# Capacitor_Thermal_Gradient_Test_Board.net
KiCad netlist of a schematic drawn in EAGLE
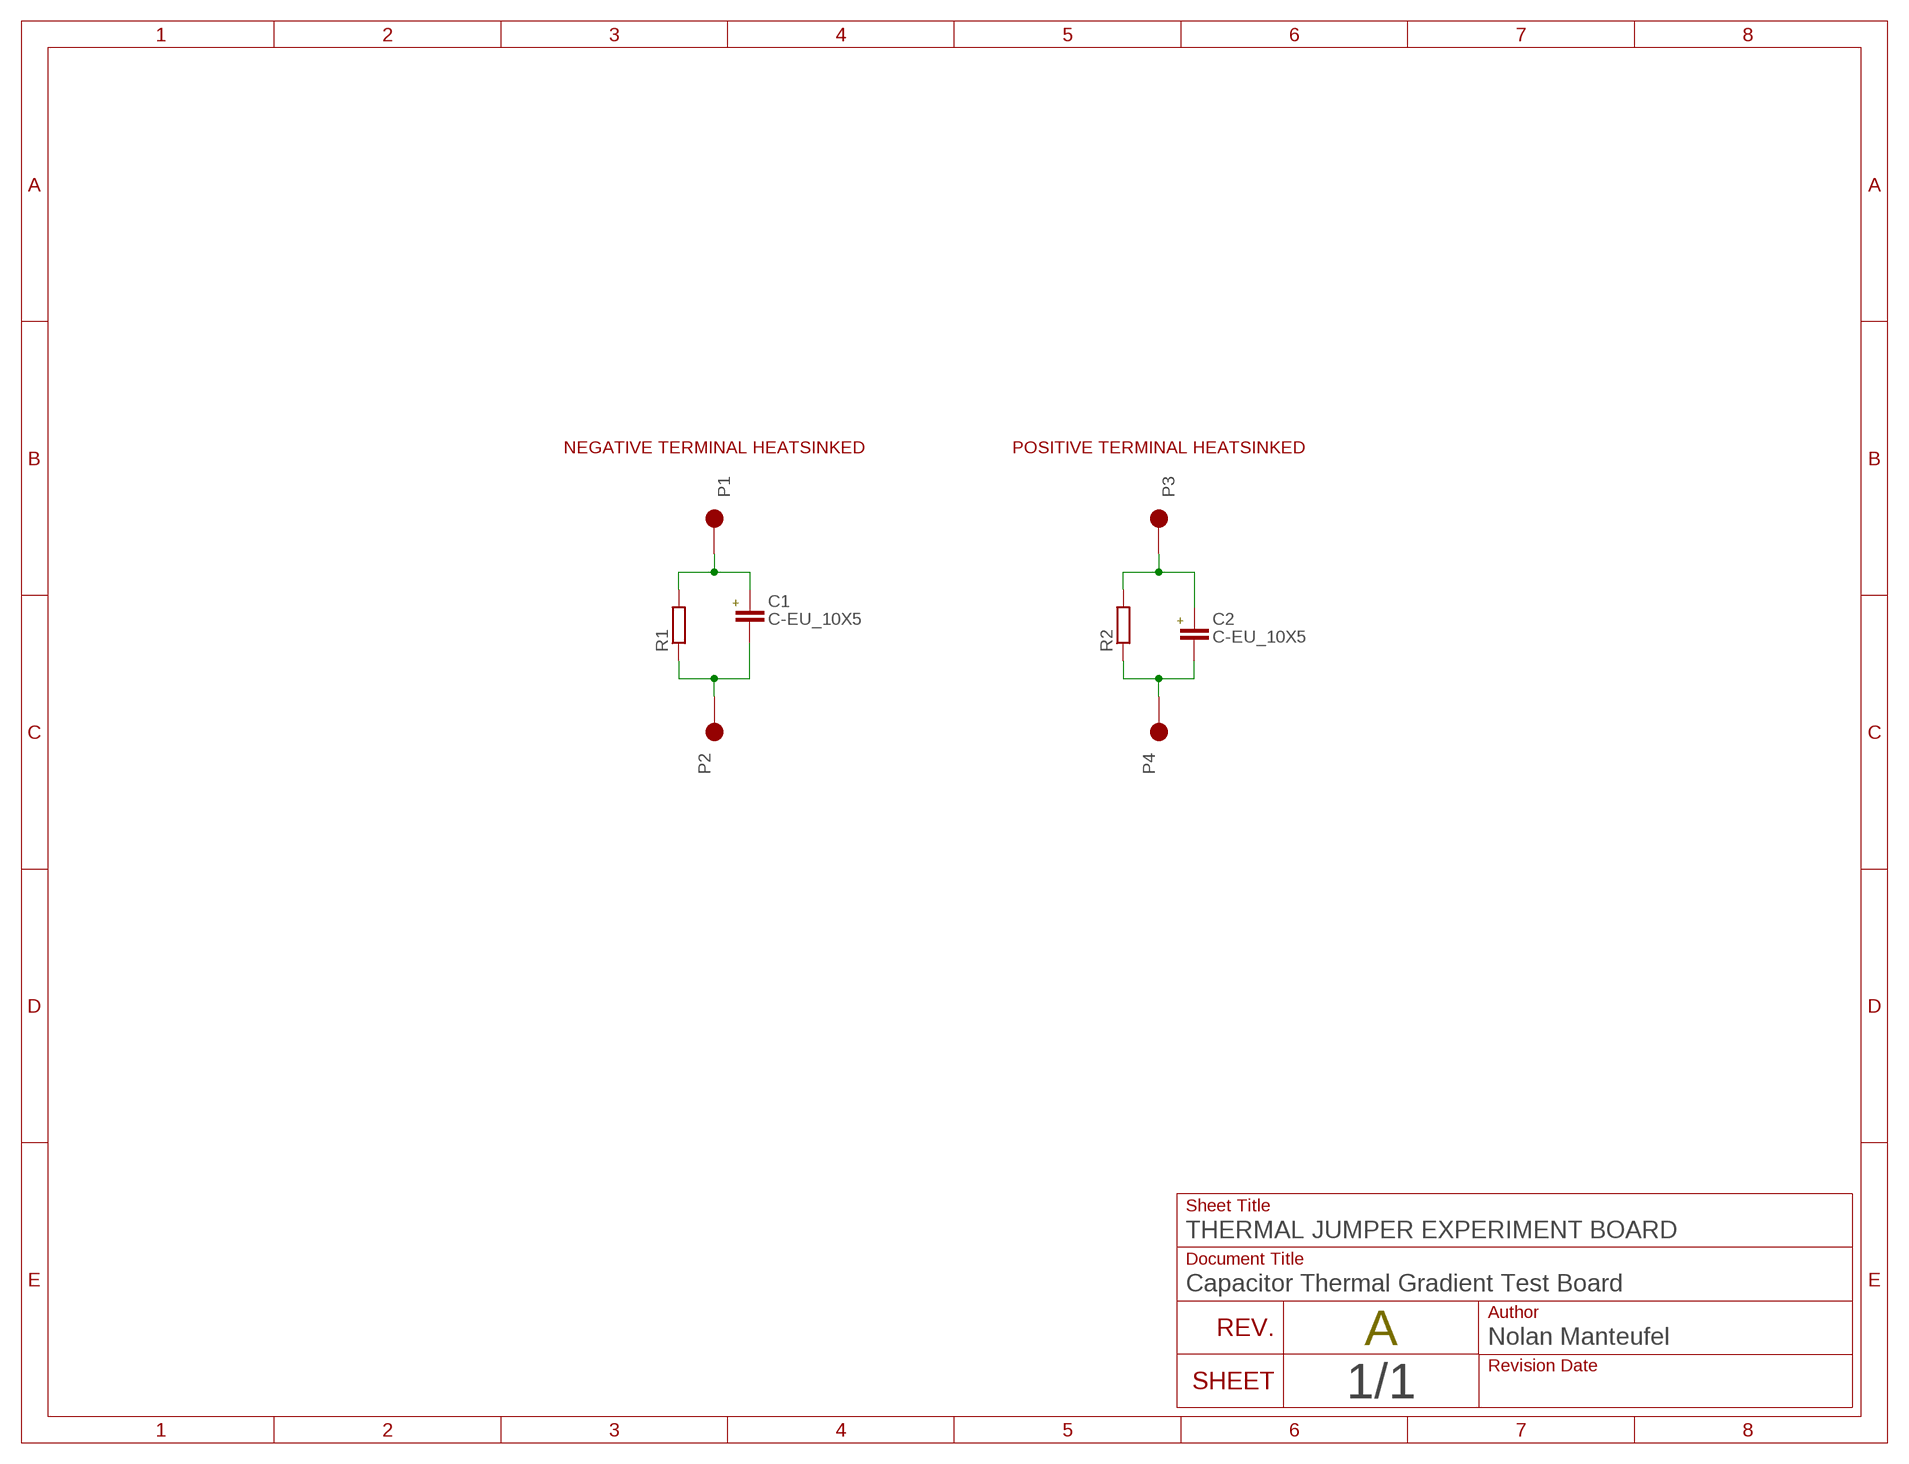
[diagram p0: schematic, sheet 1]

(export (version "E")
  (design (tool "Eeschema 10.0.6"))
  (components
    (comp (ref "C1")
      (value "C-EU_10X5")
      (footprint "eagle-import:C_PZF_10")
      (libsource (lib "eagle-import") (part "C-EU_10X5"))
    )
    (comp (ref "C2")
      (value "C-EU_10X5")
      (footprint "eagle-import:C_PZF_10")
      (libsource (lib "eagle-import") (part "C-EU_10X5"))
    )
    (comp (ref "P1")
      (value "PINS_1_2MM2")
      (footprint "eagle-import:PINS_1_2MM2")
      (libsource (lib "eagle-import") (part "PINS_1_2MM2"))
    )
    (comp (ref "P2")
      (value "PINS_1_2MM2")
      (footprint "eagle-import:PINS_1_2MM2")
      (libsource (lib "eagle-import") (part "PINS_1_2MM2"))
    )
    (comp (ref "P3")
      (value "PINS_1_2MM2")
      (footprint "eagle-import:PINS_1_2MM2")
      (libsource (lib "eagle-import") (part "PINS_1_2MM2"))
    )
    (comp (ref "P4")
      (value "PINS_1_2MM2")
      (footprint "eagle-import:PINS_1_2MM2")
      (libsource (lib "eagle-import") (part "PINS_1_2MM2"))
    )
    (comp (ref "R1")
      (value "R-EU__VISHAY_THJP1225AST1")
      (footprint "eagle-import:R_THERMAL_1225")
      (libsource (lib "eagle-import") (part "R-EU__VISHAY_THJP1225AST1"))
    )
    (comp (ref "R2")
      (value "R-EU__VISHAY_THJP1225AST1")
      (footprint "eagle-import:R_THERMAL_1225")
      (libsource (lib "eagle-import") (part "R-EU__VISHAY_THJP1225AST1"))
    )
  )
  (nets
    (net (code "1") (name "Net-(C1-1)") (class "Default")
      (node (ref "C1") (pin "1+") (pinfunction "1_1+") (pintype "passive"))
      (node (ref "P1") (pin "1") (pinfunction "1_1") (pintype "bidirectional"))
      (node (ref "R1") (pin "2") (pinfunction "2_2") (pintype "passive"))
    )
    (net (code "2") (name "Net-(C1-2)") (class "Default")
      (node (ref "C1") (pin "2-") (pinfunction "2_2-") (pintype "passive"))
      (node (ref "P2") (pin "1") (pinfunction "1_1") (pintype "bidirectional"))
      (node (ref "R1") (pin "1") (pinfunction "1_1") (pintype "passive"))
    )
    (net (code "3") (name "Net-(C2-1)") (class "Default")
      (node (ref "C2") (pin "1+") (pinfunction "1_1+") (pintype "passive"))
      (node (ref "P3") (pin "1") (pinfunction "1_1") (pintype "bidirectional"))
      (node (ref "R2") (pin "2") (pinfunction "2_2") (pintype "passive"))
    )
    (net (code "4") (name "Net-(C2-2)") (class "Default")
      (node (ref "C2") (pin "2-") (pinfunction "2_2-") (pintype "passive"))
      (node (ref "P4") (pin "1") (pinfunction "1_1") (pintype "bidirectional"))
      (node (ref "R2") (pin "1") (pinfunction "1_1") (pintype "passive"))
    )
  )
)
